# Battery_Circuit.net
KiCad netlist of a schematic drawn in Altium Designer
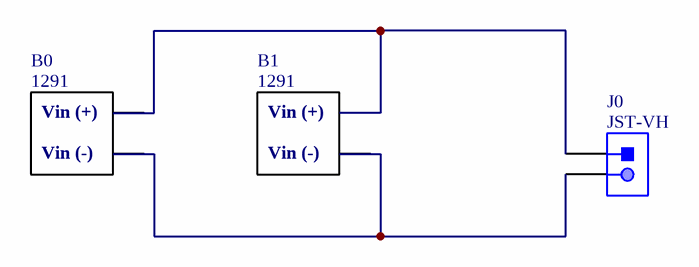
[diagram p0: Battery_Circuit.SchDoc]

(export (version "E")
  (design (tool "Eeschema 10.0.6"))
  (components
    (comp (ref "B0")
      (value "1291")
      (footprint "1291-Footprint-1")
      (description "Keystone Electronics Corp. 9 Volt Snap-In Battery Holder")
      (libsource (lib "University of Pittsburgh") (part "1291-Symbol-1"))
    )
    (comp (ref "B1")
      (value "1291")
      (footprint "1291-Footprint-1")
      (description "Keystone Electronics Corp. 9 Volt Snap-In Battery Holder")
      (libsource (lib "University of Pittsburgh") (part "1291-Symbol-1"))
    )
    (comp (ref "J0")
      (value "JST-VH")
      (footprint "JST-B2P-VH(LF)(SN)_V")
      (fields (field (name "MANUFACTURER") "JST"))
      (libsource (lib "University of Pittsburgh") (part "CN-1P-M-R2"))
    )
  )
  (nets
    (net (code "1") (name "Net-(B0-Pad0)") (class "Default")
      (node (ref "B0") (pin "0") (pintype "power_in"))
      (node (ref "B1") (pin "0") (pintype "power_in"))
      (node (ref "J0") (pin "2") (pinfunction "2_2") (pintype "passive"))
    )
    (net (code "2") (name "Net-(B0-Pad1)") (class "Default")
      (node (ref "B0") (pin "1") (pintype "power_in"))
      (node (ref "B1") (pin "1") (pintype "power_in"))
      (node (ref "J0") (pin "1") (pinfunction "1_1") (pintype "passive"))
    )
  )
)
